# beetle_drv.net
KiCad netlist of a schematic drawn in EAGLE
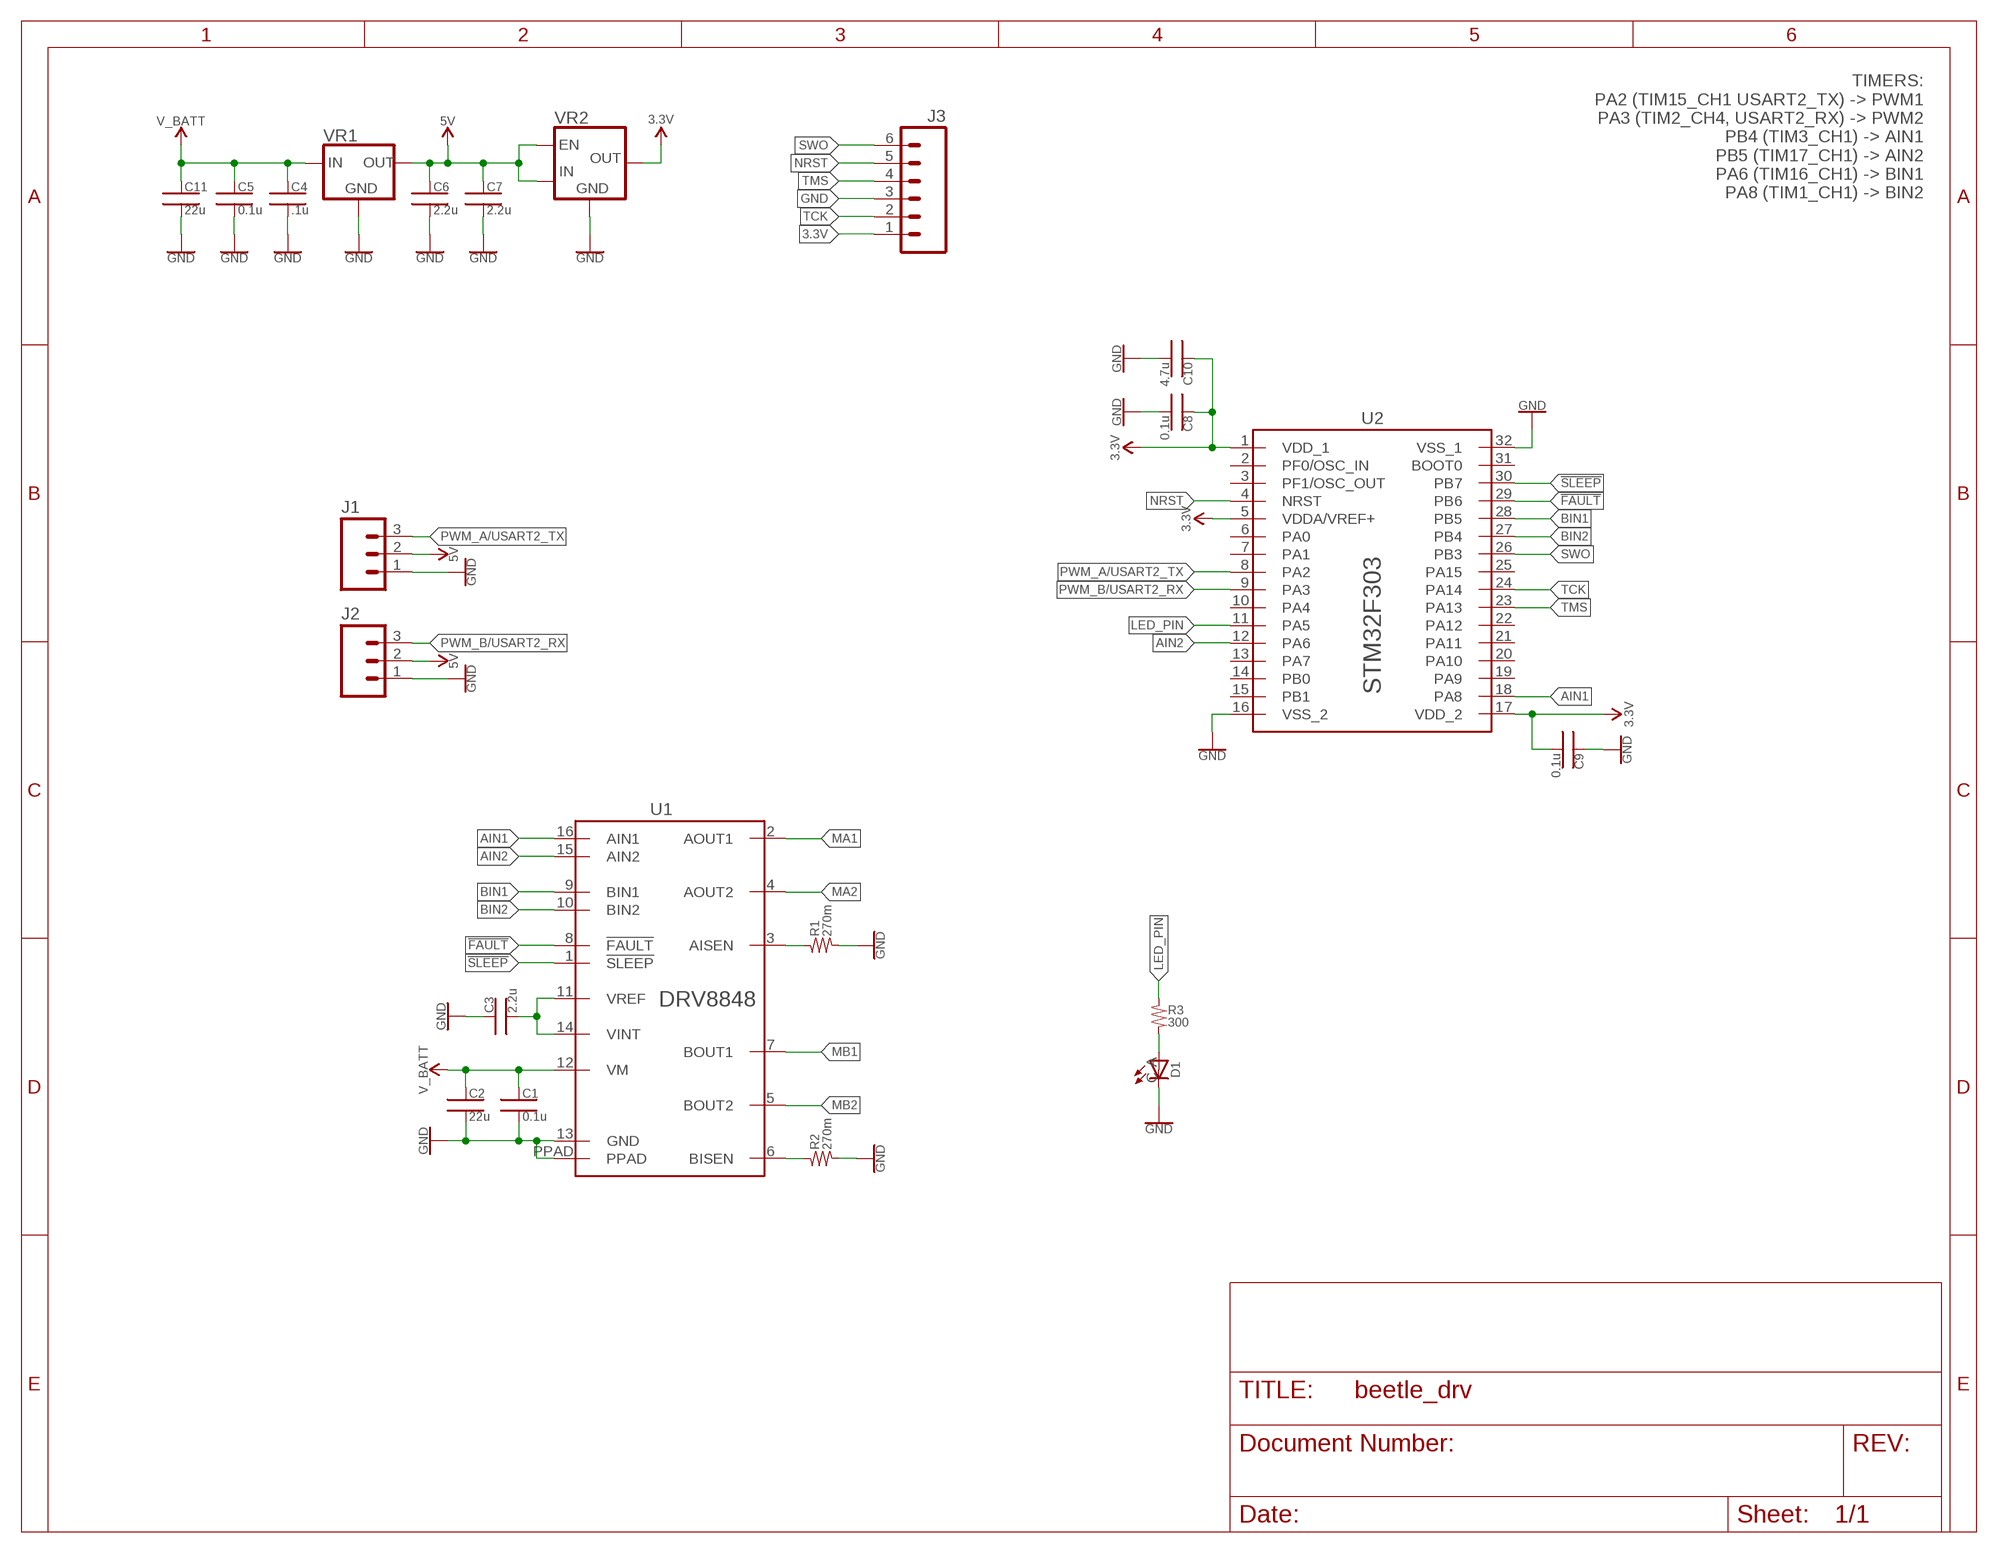
[diagram p0: schematic, sheet 1]

(export (version "E")
  (design (tool "Eeschema 10.0.6"))
  (components
    (comp (ref "C1")
      (value "0.1u")
      (footprint "eagle-import:0603")
      (libsource (lib "eagle-import") (part "CAP_SMD_0603"))
    )
    (comp (ref "C2")
      (value "22u")
      (footprint "eagle-import:1210")
      (libsource (lib "eagle-import") (part "CAP_SMD_1210"))
    )
    (comp (ref "C3")
      (value "2.2u")
      (footprint "eagle-import:0603")
      (libsource (lib "eagle-import") (part "CAP_SMD_0603"))
    )
    (comp (ref "C4")
      (value ".1u")
      (footprint "eagle-import:0603")
      (libsource (lib "eagle-import") (part "CAP_SMD_0603"))
    )
    (comp (ref "C5")
      (value "0.1u")
      (footprint "eagle-import:0603")
      (libsource (lib "eagle-import") (part "CAP_SMD_0603"))
    )
    (comp (ref "C6")
      (value "2.2u")
      (footprint "eagle-import:0603")
      (libsource (lib "eagle-import") (part "CAP_SMD_0603"))
    )
    (comp (ref "C7")
      (value "2.2u")
      (footprint "eagle-import:0603")
      (libsource (lib "eagle-import") (part "CAP_SMD_0603"))
    )
    (comp (ref "C8")
      (value "0.1u")
      (footprint "eagle-import:0603")
      (libsource (lib "eagle-import") (part "CAP_SMD_0603"))
    )
    (comp (ref "C9")
      (value "0.1u")
      (footprint "eagle-import:0603")
      (libsource (lib "eagle-import") (part "CAP_SMD_0603"))
    )
    (comp (ref "C10")
      (value "4.7u")
      (footprint "eagle-import:0603")
      (libsource (lib "eagle-import") (part "CAP_SMD_0603"))
    )
    (comp (ref "C11")
      (value "22u")
      (footprint "eagle-import:1210")
      (libsource (lib "eagle-import") (part "CAP_SMD_1210"))
    )
    (comp (ref "D1")
      (value "LED1206")
      (footprint "eagle-import:LED-1206")
      (libsource (lib "eagle-import") (part "LED1206"))
    )
    (comp (ref "J1")
      (value "M03")
      (footprint "eagle-import:1X03")
      (libsource (lib "eagle-import") (part "M03"))
    )
    (comp (ref "J2")
      (value "M03")
      (footprint "eagle-import:1X03")
      (libsource (lib "eagle-import") (part "M03"))
    )
    (comp (ref "J3")
      (value "SM06B-SRSS-TB")
      (footprint "eagle-import:SM06B-SRSS-TB")
      (libsource (lib "eagle-import") (part "?M06B-SRSS-TBS"))
    )
    (comp (ref "R1")
      (value "270m")
      (footprint "eagle-import:1210")
      (libsource (lib "eagle-import") (part "RES_SMD_1210"))
    )
    (comp (ref "R2")
      (value "270m")
      (footprint "eagle-import:1210")
      (libsource (lib "eagle-import") (part "RES_SMD_1210"))
    )
    (comp (ref "R3")
      (value "300")
      (footprint "eagle-import:0603")
      (libsource (lib "eagle-import") (part "RES_SMD_0603"))
    )
    (comp (ref "U1")
      (value "DRV8848")
      (footprint "eagle-import:PWP0016C")
      (libsource (lib "eagle-import") (part "DRV8848"))
    )
    (comp (ref "U2")
      (value "STM32F303_LQFP32")
      (footprint "eagle-import:LQFP32")
      (libsource (lib "eagle-import") (part "STM32F303_LQFP32"))
    )
    (comp (ref "VR1")
      (value "78XX_VREG_SOT223")
      (footprint "eagle-import:SOT223-4")
      (libsource (lib "eagle-import") (part "78XX_VREG_SOT223"))
    )
    (comp (ref "VR2")
      (value "TLV733P_SOT23")
      (footprint "eagle-import:SOT23-5")
      (libsource (lib "eagle-import") (part "TLV733P_SOT23"))
    )
  )
  (nets
    (net (code "1") (name "/~{FAULT}") (class "Default")
      (node (ref "U1") (pin "8") (pinfunction "~{FAULT}_8") (pintype "bidirectional"))
      (node (ref "U2") (pin "29") (pinfunction "PB6_29") (pintype "bidirectional"))
    )
    (net (code "2") (name "/~{SLEEP}") (class "Default")
      (node (ref "U1") (pin "1") (pinfunction "~{SLEEP}_1") (pintype "bidirectional"))
      (node (ref "U2") (pin "30") (pinfunction "PB7_30") (pintype "bidirectional"))
    )
    (net (code "3") (name "3.3V") (class "Default")
      (node (ref "C10") (pin "1") (pinfunction "1_1") (pintype "passive"))
      (node (ref "C8") (pin "1") (pinfunction "1_1") (pintype "passive"))
      (node (ref "C9") (pin "2") (pinfunction "2_2") (pintype "passive"))
      (node (ref "J3") (pin "1") (pinfunction "1_1") (pintype "passive"))
      (node (ref "U2") (pin "1") (pinfunction "VDD_1_1") (pintype "bidirectional"))
      (node (ref "U2") (pin "17") (pinfunction "VDD_2_17") (pintype "bidirectional"))
      (node (ref "U2") (pin "5") (pinfunction "VDDA/VREF+_5") (pintype "bidirectional"))
      (node (ref "VR2") (pin "5") (pinfunction "OUT_5") (pintype "passive"))
    )
    (net (code "4") (name "5V") (class "Default")
      (node (ref "C6") (pin "1") (pinfunction "1_1") (pintype "passive"))
      (node (ref "C7") (pin "1") (pinfunction "1_1") (pintype "passive"))
      (node (ref "J1") (pin "2") (pinfunction "2_2") (pintype "passive"))
      (node (ref "J2") (pin "2") (pinfunction "2_2") (pintype "passive"))
      (node (ref "VR1") (pin "3") (pinfunction "OUT_3") (pintype "passive"))
      (node (ref "VR2") (pin "1") (pinfunction "IN_1") (pintype "input"))
      (node (ref "VR2") (pin "3") (pinfunction "EN_3") (pintype "input"))
    )
    (net (code "5") (name "AIN1") (class "Default")
      (node (ref "U1") (pin "16") (pinfunction "AIN1_16") (pintype "bidirectional"))
      (node (ref "U2") (pin "18") (pinfunction "PA8_18") (pintype "bidirectional"))
    )
    (net (code "6") (name "AIN2") (class "Default")
      (node (ref "U1") (pin "15") (pinfunction "AIN2_15") (pintype "bidirectional"))
      (node (ref "U2") (pin "12") (pinfunction "PA6_12") (pintype "bidirectional"))
    )
    (net (code "7") (name "BIN1") (class "Default")
      (node (ref "U1") (pin "9") (pinfunction "BIN1_9") (pintype "bidirectional"))
      (node (ref "U2") (pin "28") (pinfunction "PB5_28") (pintype "bidirectional"))
    )
    (net (code "8") (name "BIN2") (class "Default")
      (node (ref "U1") (pin "10") (pinfunction "BIN2_10") (pintype "bidirectional"))
      (node (ref "U2") (pin "27") (pinfunction "PB4_27") (pintype "bidirectional"))
    )
    (net (code "9") (name "GND") (class "Default")
      (node (ref "C1") (pin "2") (pinfunction "2_2") (pintype "passive"))
      (node (ref "C10") (pin "2") (pinfunction "2_2") (pintype "passive"))
      (node (ref "C11") (pin "2") (pinfunction "2_2") (pintype "passive"))
      (node (ref "C2") (pin "2") (pinfunction "2_2") (pintype "passive"))
      (node (ref "C3") (pin "1") (pinfunction "1_1") (pintype "passive"))
      (node (ref "C4") (pin "2") (pinfunction "2_2") (pintype "passive"))
      (node (ref "C5") (pin "2") (pinfunction "2_2") (pintype "passive"))
      (node (ref "C6") (pin "2") (pinfunction "2_2") (pintype "passive"))
      (node (ref "C7") (pin "2") (pinfunction "2_2") (pintype "passive"))
      (node (ref "C8") (pin "2") (pinfunction "2_2") (pintype "passive"))
      (node (ref "C9") (pin "1") (pinfunction "1_1") (pintype "passive"))
      (node (ref "D1") (pin "C") (pinfunction "C_C") (pintype "passive"))
      (node (ref "J1") (pin "1") (pinfunction "1_1") (pintype "passive"))
      (node (ref "J2") (pin "1") (pinfunction "1_1") (pintype "passive"))
      (node (ref "J3") (pin "3") (pinfunction "3_3") (pintype "passive"))
      (node (ref "R1") (pin "2") (pinfunction "2_2") (pintype "passive"))
      (node (ref "R2") (pin "2") (pinfunction "2_2") (pintype "passive"))
      (node (ref "U1") (pin "13") (pinfunction "GND_13") (pintype "bidirectional"))
      (node (ref "U1") (pin "PPAD") (pinfunction "PPAD_PPAD") (pintype "bidirectional"))
      (node (ref "U2") (pin "16") (pinfunction "VSS_2_16") (pintype "bidirectional"))
      (node (ref "U2") (pin "32") (pinfunction "VSS_1_32") (pintype "bidirectional"))
      (node (ref "VR1") (pin "2") (pinfunction "GND_2") (pintype "input"))
      (node (ref "VR1") (pin "4") (pinfunction "GND_4") (pintype "input"))
      (node (ref "VR2") (pin "2") (pinfunction "GND_2") (pintype "input"))
      (node (ref "VR2") (pin "4") (pinfunction "GND_4") (pintype "input"))
    )
    (net (code "10") (name "LED_PIN") (class "Default")
      (node (ref "R3") (pin "1") (pinfunction "1_1") (pintype "passive"))
      (node (ref "U2") (pin "11") (pinfunction "PA5_11") (pintype "bidirectional"))
    )
    (net (code "11") (name "MA1") (class "Default")
      (node (ref "U1") (pin "2") (pinfunction "AOUT1_2") (pintype "bidirectional"))
    )
    (net (code "12") (name "MA2") (class "Default")
      (node (ref "U1") (pin "4") (pinfunction "AOUT2_4") (pintype "bidirectional"))
    )
    (net (code "13") (name "MB1") (class "Default")
      (node (ref "U1") (pin "7") (pinfunction "BOUT1_7") (pintype "bidirectional"))
    )
    (net (code "14") (name "MB2") (class "Default")
      (node (ref "U1") (pin "5") (pinfunction "BOUT2_5") (pintype "bidirectional"))
    )
    (net (code "15") (name "NRST") (class "Default")
      (node (ref "J3") (pin "5") (pinfunction "5_5") (pintype "passive"))
      (node (ref "U2") (pin "4") (pinfunction "NRST_4") (pintype "bidirectional"))
    )
    (net (code "16") (name "Net-(D1-PadA)") (class "Default")
      (node (ref "D1") (pin "A") (pinfunction "A_A") (pintype "passive"))
      (node (ref "R3") (pin "2") (pinfunction "2_2") (pintype "passive"))
    )
    (net (code "17") (name "Net-(U1-AISEN)") (class "Default")
      (node (ref "R1") (pin "1") (pinfunction "1_1") (pintype "passive"))
      (node (ref "U1") (pin "3") (pinfunction "AISEN_3") (pintype "bidirectional"))
    )
    (net (code "18") (name "Net-(U1-BISEN)") (class "Default")
      (node (ref "R2") (pin "1") (pinfunction "1_1") (pintype "passive"))
      (node (ref "U1") (pin "6") (pinfunction "BISEN_6") (pintype "bidirectional"))
    )
    (net (code "19") (name "Net-(U1-VINT)") (class "Default")
      (node (ref "C3") (pin "2") (pinfunction "2_2") (pintype "passive"))
      (node (ref "U1") (pin "11") (pinfunction "VREF_11") (pintype "bidirectional"))
      (node (ref "U1") (pin "14") (pinfunction "VINT_14") (pintype "bidirectional"))
    )
    (net (code "20") (name "PWM_A{slash}USART2_TX") (class "Default")
      (node (ref "J1") (pin "3") (pinfunction "3_3") (pintype "passive"))
      (node (ref "U2") (pin "8") (pinfunction "PA2_8") (pintype "bidirectional"))
    )
    (net (code "21") (name "PWM_B{slash}USART2_RX") (class "Default")
      (node (ref "J2") (pin "3") (pinfunction "3_3") (pintype "passive"))
      (node (ref "U2") (pin "9") (pinfunction "PA3_9") (pintype "bidirectional"))
    )
    (net (code "22") (name "SWO") (class "Default")
      (node (ref "J3") (pin "6") (pinfunction "6_6") (pintype "passive"))
      (node (ref "U2") (pin "26") (pinfunction "PB3_26") (pintype "bidirectional"))
    )
    (net (code "23") (name "TCK") (class "Default")
      (node (ref "J3") (pin "2") (pinfunction "2_2") (pintype "passive"))
      (node (ref "U2") (pin "24") (pinfunction "PA14_24") (pintype "bidirectional"))
    )
    (net (code "24") (name "TMS") (class "Default")
      (node (ref "J3") (pin "4") (pinfunction "4_4") (pintype "passive"))
      (node (ref "U2") (pin "23") (pinfunction "PA13_23") (pintype "bidirectional"))
    )
    (net (code "25") (name "V_BATT") (class "Default")
      (node (ref "C1") (pin "1") (pinfunction "1_1") (pintype "passive"))
      (node (ref "C11") (pin "1") (pinfunction "1_1") (pintype "passive"))
      (node (ref "C2") (pin "1") (pinfunction "1_1") (pintype "passive"))
      (node (ref "C4") (pin "1") (pinfunction "1_1") (pintype "passive"))
      (node (ref "C5") (pin "1") (pinfunction "1_1") (pintype "passive"))
      (node (ref "U1") (pin "12") (pinfunction "VM_12") (pintype "bidirectional"))
      (node (ref "VR1") (pin "1") (pinfunction "IN_1") (pintype "input"))
    )
    (net (code "26") (name "unconnected-(U2-BOOT0-Pad31)") (class "Default")
      (node (ref "U2") (pin "31") (pinfunction "BOOT0_31") (pintype "bidirectional"))
    )
    (net (code "27") (name "unconnected-(U2-PA0-Pad6)") (class "Default")
      (node (ref "U2") (pin "6") (pinfunction "PA0_6") (pintype "bidirectional"))
    )
    (net (code "28") (name "unconnected-(U2-PA1-Pad7)") (class "Default")
      (node (ref "U2") (pin "7") (pinfunction "PA1_7") (pintype "bidirectional"))
    )
    (net (code "29") (name "unconnected-(U2-PA4-Pad10)") (class "Default")
      (node (ref "U2") (pin "10") (pinfunction "PA4_10") (pintype "bidirectional"))
    )
    (net (code "30") (name "unconnected-(U2-PA7-Pad13)") (class "Default")
      (node (ref "U2") (pin "13") (pinfunction "PA7_13") (pintype "bidirectional"))
    )
    (net (code "31") (name "unconnected-(U2-PA9-Pad19)") (class "Default")
      (node (ref "U2") (pin "19") (pinfunction "PA9_19") (pintype "bidirectional"))
    )
    (net (code "32") (name "unconnected-(U2-PA10-Pad20)") (class "Default")
      (node (ref "U2") (pin "20") (pinfunction "PA10_20") (pintype "bidirectional"))
    )
    (net (code "33") (name "unconnected-(U2-PA11-Pad21)") (class "Default")
      (node (ref "U2") (pin "21") (pinfunction "PA11_21") (pintype "bidirectional"))
    )
    (net (code "34") (name "unconnected-(U2-PA12-Pad22)") (class "Default")
      (node (ref "U2") (pin "22") (pinfunction "PA12_22") (pintype "bidirectional"))
    )
    (net (code "35") (name "unconnected-(U2-PA15-Pad25)") (class "Default")
      (node (ref "U2") (pin "25") (pinfunction "PA15_25") (pintype "bidirectional"))
    )
    (net (code "36") (name "unconnected-(U2-PB0-Pad14)") (class "Default")
      (node (ref "U2") (pin "14") (pinfunction "PB0_14") (pintype "bidirectional"))
    )
    (net (code "37") (name "unconnected-(U2-PB1-Pad15)") (class "Default")
      (node (ref "U2") (pin "15") (pinfunction "PB1_15") (pintype "bidirectional"))
    )
    (net (code "38") (name "unconnected-(U2-PF0{slash}OSC_IN-Pad2)") (class "Default")
      (node (ref "U2") (pin "2") (pinfunction "PF0/OSC_IN_2") (pintype "bidirectional"))
    )
    (net (code "39") (name "unconnected-(U2-PF1{slash}OSC_OUT-Pad3)") (class "Default")
      (node (ref "U2") (pin "3") (pinfunction "PF1/OSC_OUT_3") (pintype "bidirectional"))
    )
  )
)
